# new.net
KiCad netlist of a schematic drawn in EAGLE
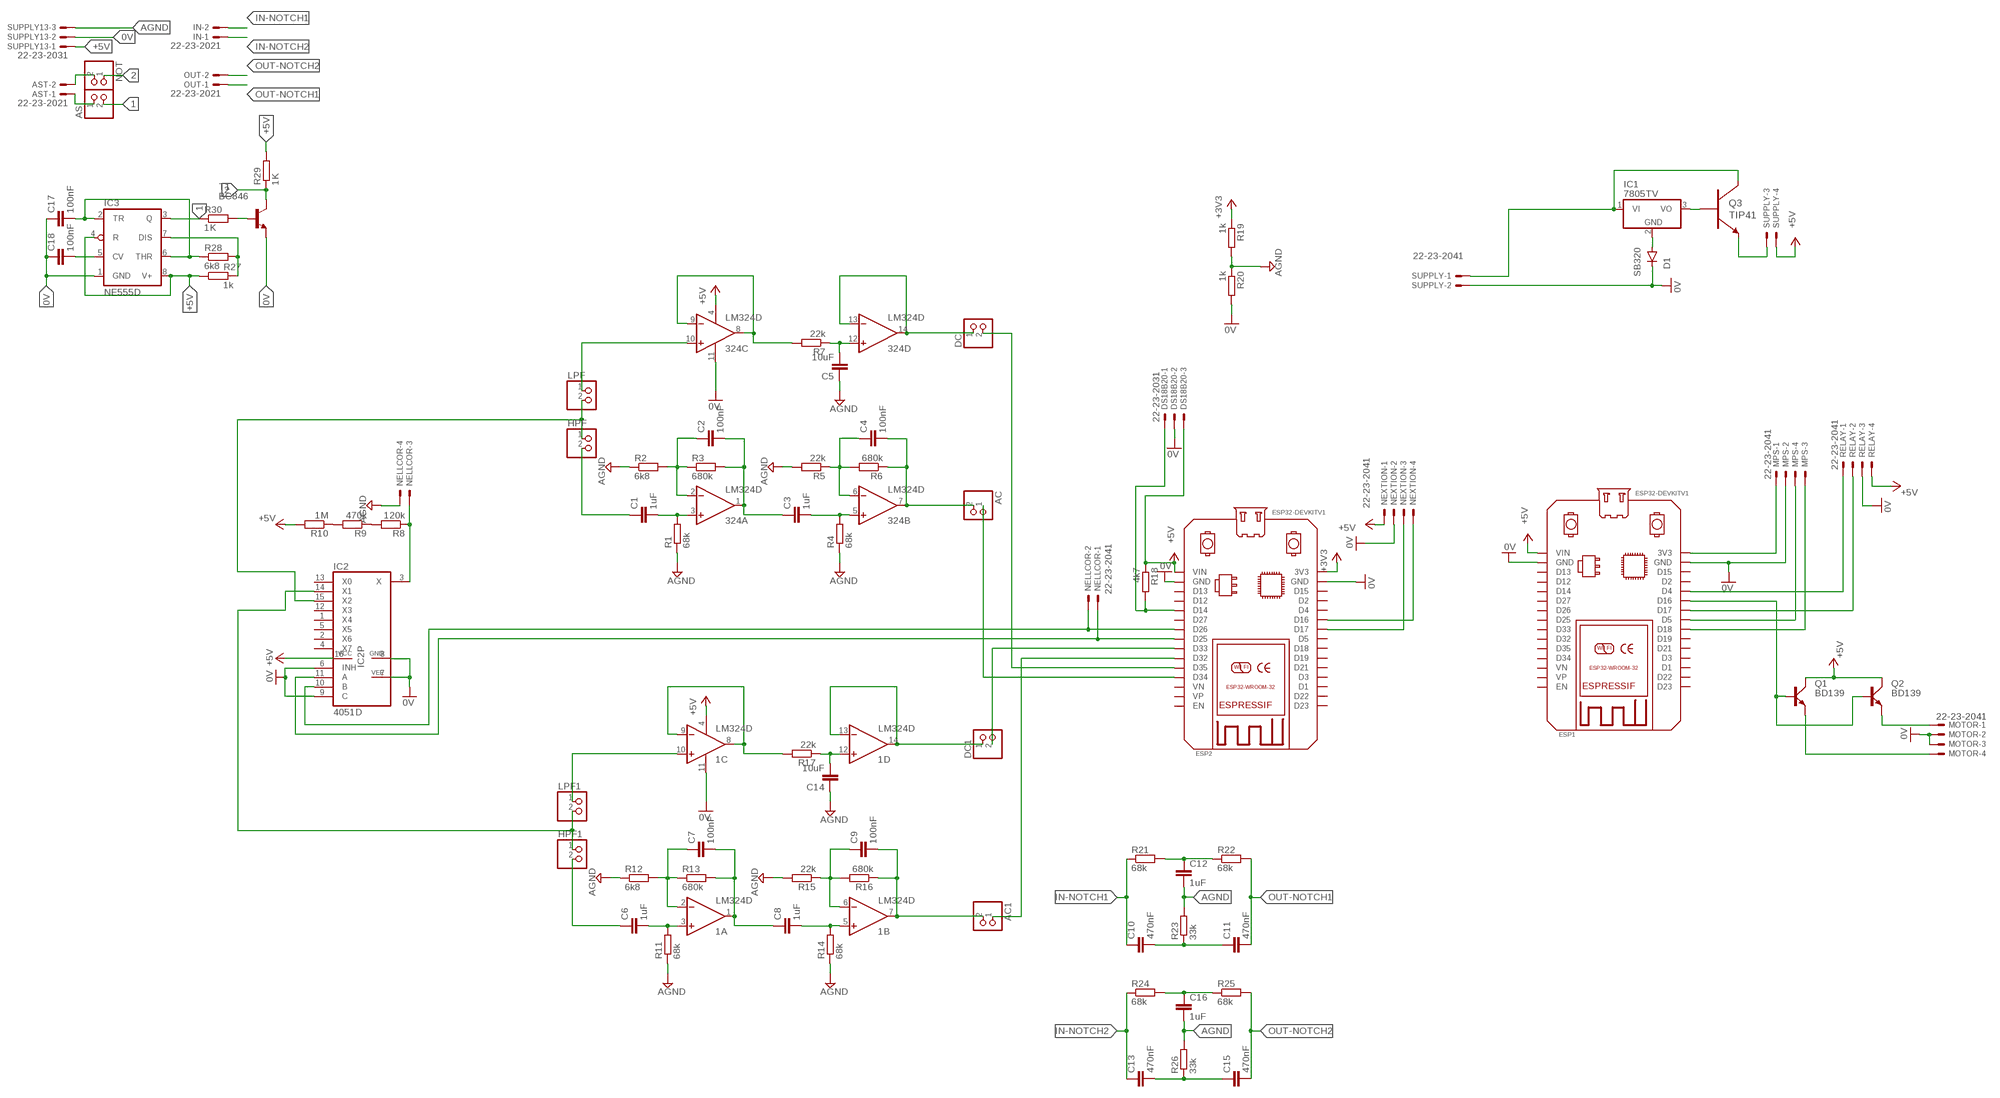
[diagram p0: schematic, sheet 1]

(export (version "E")
  (design (tool "Eeschema 10.0.6"))
  (components
    (comp (ref "1")
      (value "LM324D")
      (footprint "eagle-import:SO14")
      (libsource (lib "eagle-import") (part "LM324D"))
    )
    (comp (ref "324")
      (value "LM324D")
      (footprint "eagle-import:SO14")
      (libsource (lib "eagle-import") (part "LM324D"))
    )
    (comp (ref "AC")
      (value "PINHD-1X2")
      (footprint "eagle-import:1X02")
      (libsource (lib "eagle-import") (part "PINHD-1X2"))
    )
    (comp (ref "AC1")
      (value "PINHD-1X2")
      (footprint "eagle-import:1X02")
      (libsource (lib "eagle-import") (part "PINHD-1X2"))
    )
    (comp (ref "AS")
      (value "PINHD-1X2")
      (footprint "eagle-import:1X02")
      (libsource (lib "eagle-import") (part "PINHD-1X2"))
    )
    (comp (ref "AST")
      (value "22-23-2021")
      (footprint "eagle-import:22-23-2021")
      (fields (field (name "MF") "MOLEX"))
      (libsource (lib "eagle-import") (part "22-23-2021"))
    )
    (comp (ref "C1")
      (value "1uF")
      (footprint "eagle-import:C0603")
      (libsource (lib "eagle-import") (part "C-EUC0603"))
    )
    (comp (ref "C2")
      (value "100nF")
      (footprint "eagle-import:C0603")
      (libsource (lib "eagle-import") (part "C-EUC0603"))
    )
    (comp (ref "C3")
      (value "1uF")
      (footprint "eagle-import:C0603")
      (libsource (lib "eagle-import") (part "C-EUC0603"))
    )
    (comp (ref "C4")
      (value "100nF")
      (footprint "eagle-import:C0603")
      (libsource (lib "eagle-import") (part "C-EUC0603"))
    )
    (comp (ref "C5")
      (value "10uF")
      (footprint "eagle-import:C0603")
      (libsource (lib "eagle-import") (part "C-EUC0603"))
    )
    (comp (ref "C6")
      (value "1uF")
      (footprint "eagle-import:C0603")
      (libsource (lib "eagle-import") (part "C-EUC0603"))
    )
    (comp (ref "C7")
      (value "100nF")
      (footprint "eagle-import:C0603")
      (libsource (lib "eagle-import") (part "C-EUC0603"))
    )
    (comp (ref "C8")
      (value "1uF")
      (footprint "eagle-import:C0603")
      (libsource (lib "eagle-import") (part "C-EUC0603"))
    )
    (comp (ref "C9")
      (value "100nF")
      (footprint "eagle-import:C0603")
      (libsource (lib "eagle-import") (part "C-EUC0603"))
    )
    (comp (ref "C10")
      (value "470nF")
      (footprint "eagle-import:C0603")
      (libsource (lib "eagle-import") (part "C-EUC0603"))
    )
    (comp (ref "C11")
      (value "470nF")
      (footprint "eagle-import:C0603")
      (libsource (lib "eagle-import") (part "C-EUC0603"))
    )
    (comp (ref "C12")
      (value "1uF")
      (footprint "eagle-import:C0603")
      (libsource (lib "eagle-import") (part "C-EUC0603"))
    )
    (comp (ref "C13")
      (value "470nF")
      (footprint "eagle-import:C0603")
      (libsource (lib "eagle-import") (part "C-EUC0603"))
    )
    (comp (ref "C14")
      (value "10uF")
      (footprint "eagle-import:C0603")
      (libsource (lib "eagle-import") (part "C-EUC0603"))
    )
    (comp (ref "C15")
      (value "470nF")
      (footprint "eagle-import:C0603")
      (libsource (lib "eagle-import") (part "C-EUC0603"))
    )
    (comp (ref "C16")
      (value "1uF")
      (footprint "eagle-import:C0603")
      (libsource (lib "eagle-import") (part "C-EUC0603"))
    )
    (comp (ref "C17")
      (value "100nF")
      (footprint "eagle-import:C0603")
      (libsource (lib "eagle-import") (part "C-EUC0603"))
    )
    (comp (ref "C18")
      (value "100nF")
      (footprint "eagle-import:C0603")
      (libsource (lib "eagle-import") (part "C-EUC0603"))
    )
    (comp (ref "D1")
      (value "SB320")
      (footprint "eagle-import:DO201-15")
      (libsource (lib "eagle-import") (part "SB320"))
    )
    (comp (ref "DC")
      (value "PINHD-1X2")
      (footprint "eagle-import:1X02")
      (libsource (lib "eagle-import") (part "PINHD-1X2"))
    )
    (comp (ref "DC1")
      (value "PINHD-1X2")
      (footprint "eagle-import:1X02")
      (libsource (lib "eagle-import") (part "PINHD-1X2"))
    )
    (comp (ref "DS18B20")
      (value "22-23-2031")
      (footprint "eagle-import:22-23-2031")
      (fields (field (name "MF") "MOLEX"))
      (libsource (lib "eagle-import") (part "22-23-2031"))
    )
    (comp (ref "ESP1")
      (value "ESP32DEVKITV1")
      (footprint "eagle-import:ESP32-DEVKITV1")
      (libsource (lib "eagle-import") (part "ESP32DEVKITV1"))
    )
    (comp (ref "ESP2")
      (value "ESP32DEVKITV1")
      (footprint "eagle-import:ESP32-DEVKITV1")
      (libsource (lib "eagle-import") (part "ESP32DEVKITV1"))
    )
    (comp (ref "HPF")
      (value "PINHD-1X2")
      (footprint "eagle-import:1X02")
      (libsource (lib "eagle-import") (part "PINHD-1X2"))
    )
    (comp (ref "HPF1")
      (value "PINHD-1X2")
      (footprint "eagle-import:1X02")
      (libsource (lib "eagle-import") (part "PINHD-1X2"))
    )
    (comp (ref "IC1")
      (value "7805TV")
      (footprint "eagle-import:TO220V")
      (libsource (lib "eagle-import") (part "78TV05"))
    )
    (comp (ref "IC2")
      (value "4051D")
      (footprint "eagle-import:SO16")
      (libsource (lib "eagle-import") (part "4051D"))
    )
    (comp (ref "IC3")
      (value "NE555D")
      (footprint "eagle-import:SO08")
      (libsource (lib "eagle-import") (part "555DNE"))
    )
    (comp (ref "IN")
      (value "22-23-2021")
      (footprint "eagle-import:22-23-2021")
      (fields (field (name "MF") "MOLEX"))
      (libsource (lib "eagle-import") (part "22-23-2021"))
    )
    (comp (ref "LPF")
      (value "PINHD-1X2")
      (footprint "eagle-import:1X02")
      (libsource (lib "eagle-import") (part "PINHD-1X2"))
    )
    (comp (ref "LPF1")
      (value "PINHD-1X2")
      (footprint "eagle-import:1X02")
      (libsource (lib "eagle-import") (part "PINHD-1X2"))
    )
    (comp (ref "MOTOR")
      (value "22-23-2041")
      (footprint "eagle-import:22-23-2041")
      (fields (field (name "MF") "MOLEX"))
      (libsource (lib "eagle-import") (part "22-23-2041"))
    )
    (comp (ref "MPS")
      (value "22-23-2041")
      (footprint "eagle-import:22-23-2041")
      (fields (field (name "MF") "MOLEX"))
      (libsource (lib "eagle-import") (part "22-23-2041"))
    )
    (comp (ref "NELLCOR")
      (value "22-23-2041")
      (footprint "eagle-import:22-23-2041")
      (fields (field (name "MF") "MOLEX"))
      (libsource (lib "eagle-import") (part "22-23-2041"))
    )
    (comp (ref "NEXTION")
      (value "22-23-2041")
      (footprint "eagle-import:22-23-2041")
      (fields (field (name "MF") "MOLEX"))
      (libsource (lib "eagle-import") (part "22-23-2041"))
    )
    (comp (ref "NOT")
      (value "PINHD-1X2")
      (footprint "eagle-import:1X02")
      (libsource (lib "eagle-import") (part "PINHD-1X2"))
    )
    (comp (ref "OUT")
      (value "22-23-2021")
      (footprint "eagle-import:22-23-2021")
      (fields (field (name "MF") "MOLEX"))
      (libsource (lib "eagle-import") (part "22-23-2021"))
    )
    (comp (ref "Q1")
      (value "BD139")
      (footprint "eagle-import:TO126AV")
      (libsource (lib "eagle-import") (part "BD139"))
    )
    (comp (ref "Q2")
      (value "BD139")
      (footprint "eagle-import:TO126AV")
      (libsource (lib "eagle-import") (part "BD139"))
    )
    (comp (ref "Q3")
      (value "TIP41")
      (footprint "eagle-import:TO-220AB")
      (fields (field (name "MF") "ON Semiconductor"))
      (libsource (lib "eagle-import") (part "TIP41"))
    )
    (comp (ref "R1")
      (value "68k")
      (footprint "eagle-import:R0603")
      (libsource (lib "eagle-import") (part "R-EU_R0603"))
    )
    (comp (ref "R2")
      (value "6k8")
      (footprint "eagle-import:R0603")
      (libsource (lib "eagle-import") (part "R-EU_R0603"))
    )
    (comp (ref "R3")
      (value "680k")
      (footprint "eagle-import:R0603")
      (libsource (lib "eagle-import") (part "R-EU_R0603"))
    )
    (comp (ref "R4")
      (value "68k")
      (footprint "eagle-import:R0603")
      (libsource (lib "eagle-import") (part "R-EU_R0603"))
    )
    (comp (ref "R5")
      (value "22k")
      (footprint "eagle-import:R0603")
      (libsource (lib "eagle-import") (part "R-EU_R0603"))
    )
    (comp (ref "R6")
      (value "680k")
      (footprint "eagle-import:R0603")
      (libsource (lib "eagle-import") (part "R-EU_R0603"))
    )
    (comp (ref "R7")
      (value "22k")
      (footprint "eagle-import:R0603")
      (libsource (lib "eagle-import") (part "R-EU_R0603"))
    )
    (comp (ref "R8")
      (value "120k")
      (footprint "eagle-import:R0603")
      (libsource (lib "eagle-import") (part "R-EU_R0603"))
    )
    (comp (ref "R9")
      (value "470k")
      (footprint "eagle-import:R0603")
      (libsource (lib "eagle-import") (part "R-EU_R0603"))
    )
    (comp (ref "R10")
      (value "1M")
      (footprint "eagle-import:R0603")
      (libsource (lib "eagle-import") (part "R-EU_R0603"))
    )
    (comp (ref "R11")
      (value "68k")
      (footprint "eagle-import:R0603")
      (libsource (lib "eagle-import") (part "R-EU_R0603"))
    )
    (comp (ref "R12")
      (value "6k8")
      (footprint "eagle-import:R0603")
      (libsource (lib "eagle-import") (part "R-EU_R0603"))
    )
    (comp (ref "R13")
      (value "680k")
      (footprint "eagle-import:R0603")
      (libsource (lib "eagle-import") (part "R-EU_R0603"))
    )
    (comp (ref "R14")
      (value "68k")
      (footprint "eagle-import:R0603")
      (libsource (lib "eagle-import") (part "R-EU_R0603"))
    )
    (comp (ref "R15")
      (value "22k")
      (footprint "eagle-import:R0603")
      (libsource (lib "eagle-import") (part "R-EU_R0603"))
    )
    (comp (ref "R16")
      (value "680k")
      (footprint "eagle-import:R0603")
      (libsource (lib "eagle-import") (part "R-EU_R0603"))
    )
    (comp (ref "R17")
      (value "22k")
      (footprint "eagle-import:R0603")
      (libsource (lib "eagle-import") (part "R-EU_R0603"))
    )
    (comp (ref "R18")
      (value "4k7")
      (footprint "eagle-import:R0603")
      (libsource (lib "eagle-import") (part "R-EU_R0603"))
    )
    (comp (ref "R19")
      (value "1k")
      (footprint "eagle-import:R0603")
      (libsource (lib "eagle-import") (part "R-EU_R0603"))
    )
    (comp (ref "R20")
      (value "1k")
      (footprint "eagle-import:R0603")
      (libsource (lib "eagle-import") (part "R-EU_R0603"))
    )
    (comp (ref "R21")
      (value "68k")
      (footprint "eagle-import:R0603")
      (libsource (lib "eagle-import") (part "R-EU_R0603"))
    )
    (comp (ref "R22")
      (value "68k")
      (footprint "eagle-import:R0603")
      (libsource (lib "eagle-import") (part "R-EU_R0603"))
    )
    (comp (ref "R23")
      (value "33k")
      (footprint "eagle-import:R0603")
      (libsource (lib "eagle-import") (part "R-EU_R0603"))
    )
    (comp (ref "R24")
      (value "68k")
      (footprint "eagle-import:R0603")
      (libsource (lib "eagle-import") (part "R-EU_R0603"))
    )
    (comp (ref "R25")
      (value "68k")
      (footprint "eagle-import:R0603")
      (libsource (lib "eagle-import") (part "R-EU_R0603"))
    )
    (comp (ref "R26")
      (value "33k")
      (footprint "eagle-import:R0603")
      (libsource (lib "eagle-import") (part "R-EU_R0603"))
    )
    (comp (ref "R27")
      (value "1k")
      (footprint "eagle-import:R0603")
      (libsource (lib "eagle-import") (part "R-EU_R0603"))
    )
    (comp (ref "R28")
      (value "6k8")
      (footprint "eagle-import:R0603")
      (libsource (lib "eagle-import") (part "R-EU_R0603"))
    )
    (comp (ref "R29")
      (value "1K")
      (footprint "eagle-import:R0603")
      (libsource (lib "eagle-import") (part "R-EU_R0603"))
    )
    (comp (ref "R30")
      (value "1K")
      (footprint "eagle-import:R0603")
      (libsource (lib "eagle-import") (part "R-EU_R0603"))
    )
    (comp (ref "RELAY")
      (value "22-23-2041")
      (footprint "eagle-import:22-23-2041")
      (fields (field (name "MF") "MOLEX"))
      (libsource (lib "eagle-import") (part "22-23-2041"))
    )
    (comp (ref "SUPPLY")
      (value "22-23-2041")
      (footprint "eagle-import:22-23-2041")
      (fields (field (name "MF") "MOLEX"))
      (libsource (lib "eagle-import") (part "22-23-2041"))
    )
    (comp (ref "SUPPLY13")
      (value "22-23-2031")
      (footprint "eagle-import:22-23-2031")
      (fields (field (name "MF") "MOLEX"))
      (libsource (lib "eagle-import") (part "22-23-2031"))
    )
    (comp (ref "T1")
      (value "BC846")
      (footprint "eagle-import:SOT23")
      (libsource (lib "eagle-import") (part "BC846"))
    )
  )
  (nets
    (net (code "1") (name "+3V3") (class "Default")
      (node (ref "ESP2") (pin "3V3") (pinfunction "3V3_3V3") (pintype "bidirectional"))
      (node (ref "R19") (pin "1") (pinfunction "1_1") (pintype "passive"))
    )
    (net (code "2") (name "+5V") (class "Default")
      (node (ref "1") (pin "4") (pinfunction "V+_4") (pintype "power_in"))
      (node (ref "324") (pin "4") (pinfunction "V+_4") (pintype "power_in"))
      (node (ref "DS18B20") (pin "3") (pinfunction "S_3") (pintype "passive"))
      (node (ref "ESP1") (pin "VIN") (pinfunction "VIN_VIN") (pintype "bidirectional"))
      (node (ref "ESP2") (pin "VIN") (pinfunction "VIN_VIN") (pintype "bidirectional"))
      (node (ref "IC2") (pin "16") (pinfunction "VCC_16") (pintype "power_in"))
      (node (ref "IC3") (pin "4") (pinfunction "R_4") (pintype "input"))
      (node (ref "IC3") (pin "8") (pinfunction "V+_8") (pintype "power_in"))
      (node (ref "NEXTION") (pin "1") (pinfunction "S_1") (pintype "passive"))
      (node (ref "Q1") (pin "C") (pinfunction "C_C") (pintype "passive"))
      (node (ref "Q2") (pin "C") (pinfunction "C_C") (pintype "passive"))
      (node (ref "R10") (pin "2") (pinfunction "2_2") (pintype "passive"))
      (node (ref "R18") (pin "1") (pinfunction "1_1") (pintype "passive"))
      (node (ref "R27") (pin "1") (pinfunction "1_1") (pintype "passive"))
      (node (ref "R29") (pin "2") (pinfunction "2_2") (pintype "passive"))
      (node (ref "RELAY") (pin "4") (pinfunction "S_4") (pintype "passive"))
      (node (ref "SUPPLY") (pin "4") (pinfunction "S_4") (pintype "passive"))
      (node (ref "SUPPLY13") (pin "1") (pinfunction "S_1") (pintype "passive"))
    )
    (net (code "3") (name "0V") (class "Default")
      (node (ref "1") (pin "11") (pinfunction "V-_11") (pintype "power_in"))
      (node (ref "324") (pin "11") (pinfunction "V-_11") (pintype "power_in"))
      (node (ref "C17") (pin "1") (pinfunction "1_1") (pintype "passive"))
      (node (ref "C18") (pin "1") (pinfunction "1_1") (pintype "passive"))
      (node (ref "D1") (pin "C") (pinfunction "C_C") (pintype "passive"))
      (node (ref "DS18B20") (pin "2") (pinfunction "S_2") (pintype "passive"))
      (node (ref "ESP1") (pin "GND") (pinfunction "GND_GND") (pintype "bidirectional"))
      (node (ref "ESP1") (pin "GND@1") (pinfunction "GND_GND@1") (pintype "bidirectional"))
      (node (ref "ESP2") (pin "GND") (pinfunction "GND_GND") (pintype "bidirectional"))
      (node (ref "ESP2") (pin "GND@1") (pinfunction "GND_GND@1") (pintype "bidirectional"))
      (node (ref "IC2") (pin "6") (pinfunction "INH_6") (pintype "input"))
      (node (ref "IC2") (pin "7") (pinfunction "VEE_7") (pintype "power_in"))
      (node (ref "IC2") (pin "8") (pinfunction "GND_8") (pintype "power_in"))
      (node (ref "IC2") (pin "9") (pinfunction "C_9") (pintype "input"))
      (node (ref "IC3") (pin "1") (pinfunction "GND_1") (pintype "power_in"))
      (node (ref "MOTOR") (pin "2") (pinfunction "S_2") (pintype "passive"))
      (node (ref "MOTOR") (pin "3") (pinfunction "S_3") (pintype "passive"))
      (node (ref "MPS") (pin "2") (pinfunction "S_2") (pintype "passive"))
      (node (ref "NEXTION") (pin "2") (pinfunction "S_2") (pintype "passive"))
      (node (ref "R20") (pin "2") (pinfunction "2_2") (pintype "passive"))
      (node (ref "RELAY") (pin "3") (pinfunction "S_3") (pintype "passive"))
      (node (ref "SUPPLY") (pin "2") (pinfunction "S_2") (pintype "passive"))
      (node (ref "SUPPLY13") (pin "2") (pinfunction "S_2") (pintype "passive"))
      (node (ref "T1") (pin "2") (pinfunction "E_2") (pintype "passive"))
    )
    (net (code "4") (name "1") (class "Default")
      (node (ref "AS") (pin "2") (pinfunction "2_2") (pintype "passive"))
      (node (ref "IC3") (pin "3") (pinfunction "Q_3") (pintype "output"))
      (node (ref "R30") (pin "1") (pinfunction "1_1") (pintype "passive"))
    )
    (net (code "5") (name "2") (class "Default")
      (node (ref "NOT") (pin "1") (pinfunction "1_1") (pintype "passive"))
      (node (ref "R29") (pin "1") (pinfunction "1_1") (pintype "passive"))
      (node (ref "T1") (pin "3") (pinfunction "C_3") (pintype "passive"))
    )
    (net (code "6") (name "AGND") (class "Default")
      (node (ref "C12") (pin "2") (pinfunction "2_2") (pintype "passive"))
      (node (ref "C14") (pin "1") (pinfunction "1_1") (pintype "passive"))
      (node (ref "C16") (pin "2") (pinfunction "2_2") (pintype "passive"))
      (node (ref "C5") (pin "1") (pinfunction "1_1") (pintype "passive"))
      (node (ref "NELLCOR") (pin "4") (pinfunction "S_4") (pintype "passive"))
      (node (ref "R1") (pin "1") (pinfunction "1_1") (pintype "passive"))
      (node (ref "R11") (pin "1") (pinfunction "1_1") (pintype "passive"))
      (node (ref "R12") (pin "1") (pinfunction "1_1") (pintype "passive"))
      (node (ref "R14") (pin "1") (pinfunction "1_1") (pintype "passive"))
      (node (ref "R15") (pin "2") (pinfunction "2_2") (pintype "passive"))
      (node (ref "R19") (pin "2") (pinfunction "2_2") (pintype "passive"))
      (node (ref "R2") (pin "1") (pinfunction "1_1") (pintype "passive"))
      (node (ref "R20") (pin "1") (pinfunction "1_1") (pintype "passive"))
      (node (ref "R23") (pin "2") (pinfunction "2_2") (pintype "passive"))
      (node (ref "R26") (pin "2") (pinfunction "2_2") (pintype "passive"))
      (node (ref "R4") (pin "1") (pinfunction "1_1") (pintype "passive"))
      (node (ref "R5") (pin "2") (pinfunction "2_2") (pintype "passive"))
      (node (ref "SUPPLY13") (pin "3") (pinfunction "S_3") (pintype "passive"))
    )
    (net (code "7") (name "IN-NOTCH1") (class "Default")
      (node (ref "C10") (pin "1") (pinfunction "1_1") (pintype "passive"))
      (node (ref "IN") (pin "2") (pinfunction "S_2") (pintype "passive"))
      (node (ref "R21") (pin "1") (pinfunction "1_1") (pintype "passive"))
    )
    (net (code "8") (name "IN-NOTCH2") (class "Default")
      (node (ref "C13") (pin "1") (pinfunction "1_1") (pintype "passive"))
      (node (ref "IN") (pin "1") (pinfunction "S_1") (pintype "passive"))
      (node (ref "R24") (pin "1") (pinfunction "1_1") (pintype "passive"))
    )
    (net (code "9") (name "Net-(1A-+IN)") (class "Default")
      (node (ref "1") (pin "3") (pinfunction "+IN_3") (pintype "input"))
      (node (ref "C6") (pin "2") (pinfunction "2_2") (pintype "passive"))
      (node (ref "R11") (pin "2") (pinfunction "2_2") (pintype "passive"))
    )
    (net (code "10") (name "Net-(1A--IN)") (class "Default")
      (node (ref "1") (pin "2") (pinfunction "-IN_2") (pintype "input"))
      (node (ref "C7") (pin "1") (pinfunction "1_1") (pintype "passive"))
      (node (ref "R12") (pin "2") (pinfunction "2_2") (pintype "passive"))
      (node (ref "R13") (pin "1") (pinfunction "1_1") (pintype "passive"))
    )
    (net (code "11") (name "Net-(1A-OUT)") (class "Default")
      (node (ref "1") (pin "1") (pinfunction "OUT_1") (pintype "output"))
      (node (ref "C7") (pin "2") (pinfunction "2_2") (pintype "passive"))
      (node (ref "C8") (pin "1") (pinfunction "1_1") (pintype "passive"))
      (node (ref "R13") (pin "2") (pinfunction "2_2") (pintype "passive"))
    )
    (net (code "12") (name "Net-(1B-+IN)") (class "Default")
      (node (ref "1") (pin "5") (pinfunction "+IN_5") (pintype "input"))
      (node (ref "C8") (pin "2") (pinfunction "2_2") (pintype "passive"))
      (node (ref "R14") (pin "2") (pinfunction "2_2") (pintype "passive"))
    )
    (net (code "13") (name "Net-(1B--IN)") (class "Default")
      (node (ref "1") (pin "6") (pinfunction "-IN_6") (pintype "input"))
      (node (ref "C9") (pin "1") (pinfunction "1_1") (pintype "passive"))
      (node (ref "R15") (pin "1") (pinfunction "1_1") (pintype "passive"))
      (node (ref "R16") (pin "2") (pinfunction "2_2") (pintype "passive"))
    )
    (net (code "14") (name "Net-(1B-OUT)") (class "Default")
      (node (ref "1") (pin "7") (pinfunction "OUT_7") (pintype "output"))
      (node (ref "AC1") (pin "2") (pinfunction "2_2") (pintype "passive"))
      (node (ref "C9") (pin "2") (pinfunction "2_2") (pintype "passive"))
      (node (ref "R16") (pin "1") (pinfunction "1_1") (pintype "passive"))
    )
    (net (code "15") (name "Net-(1C-+IN)") (class "Default")
      (node (ref "1") (pin "10") (pinfunction "+IN_10") (pintype "input"))
      (node (ref "LPF1") (pin "1") (pinfunction "1_1") (pintype "passive"))
    )
    (net (code "16") (name "Net-(1C--IN)") (class "Default")
      (node (ref "1") (pin "8") (pinfunction "OUT_8") (pintype "output"))
      (node (ref "1") (pin "9") (pinfunction "-IN_9") (pintype "input"))
      (node (ref "R17") (pin "2") (pinfunction "2_2") (pintype "passive"))
    )
    (net (code "17") (name "Net-(1D-+IN)") (class "Default")
      (node (ref "1") (pin "12") (pinfunction "+IN_12") (pintype "input"))
      (node (ref "C14") (pin "2") (pinfunction "2_2") (pintype "passive"))
      (node (ref "R17") (pin "1") (pinfunction "1_1") (pintype "passive"))
    )
    (net (code "18") (name "Net-(1D--IN)") (class "Default")
      (node (ref "1") (pin "13") (pinfunction "-IN_13") (pintype "input"))
      (node (ref "1") (pin "14") (pinfunction "OUT_14") (pintype "output"))
      (node (ref "DC1") (pin "1") (pinfunction "1_1") (pintype "passive"))
    )
    (net (code "19") (name "Net-(324A-+IN)") (class "Default")
      (node (ref "324") (pin "3") (pinfunction "+IN_3") (pintype "input"))
      (node (ref "C1") (pin "2") (pinfunction "2_2") (pintype "passive"))
      (node (ref "R1") (pin "2") (pinfunction "2_2") (pintype "passive"))
    )
    (net (code "20") (name "Net-(324A--IN)") (class "Default")
      (node (ref "324") (pin "2") (pinfunction "-IN_2") (pintype "input"))
      (node (ref "C2") (pin "1") (pinfunction "1_1") (pintype "passive"))
      (node (ref "R2") (pin "2") (pinfunction "2_2") (pintype "passive"))
      (node (ref "R3") (pin "1") (pinfunction "1_1") (pintype "passive"))
    )
    (net (code "21") (name "Net-(324A-OUT)") (class "Default")
      (node (ref "324") (pin "1") (pinfunction "OUT_1") (pintype "output"))
      (node (ref "C2") (pin "2") (pinfunction "2_2") (pintype "passive"))
      (node (ref "C3") (pin "1") (pinfunction "1_1") (pintype "passive"))
      (node (ref "R3") (pin "2") (pinfunction "2_2") (pintype "passive"))
    )
    (net (code "22") (name "Net-(324B-+IN)") (class "Default")
      (node (ref "324") (pin "5") (pinfunction "+IN_5") (pintype "input"))
      (node (ref "C3") (pin "2") (pinfunction "2_2") (pintype "passive"))
      (node (ref "R4") (pin "2") (pinfunction "2_2") (pintype "passive"))
    )
    (net (code "23") (name "Net-(324B--IN)") (class "Default")
      (node (ref "324") (pin "6") (pinfunction "-IN_6") (pintype "input"))
      (node (ref "C4") (pin "1") (pinfunction "1_1") (pintype "passive"))
      (node (ref "R5") (pin "1") (pinfunction "1_1") (pintype "passive"))
      (node (ref "R6") (pin "2") (pinfunction "2_2") (pintype "passive"))
    )
    (net (code "24") (name "Net-(324B-OUT)") (class "Default")
      (node (ref "324") (pin "7") (pinfunction "OUT_7") (pintype "output"))
      (node (ref "AC") (pin "2") (pinfunction "2_2") (pintype "passive"))
      (node (ref "C4") (pin "2") (pinfunction "2_2") (pintype "passive"))
      (node (ref "R6") (pin "1") (pinfunction "1_1") (pintype "passive"))
    )
    (net (code "25") (name "Net-(324C-+IN)") (class "Default")
      (node (ref "324") (pin "10") (pinfunction "+IN_10") (pintype "input"))
      (node (ref "LPF") (pin "1") (pinfunction "1_1") (pintype "passive"))
    )
    (net (code "26") (name "Net-(324C--IN)") (class "Default")
      (node (ref "324") (pin "8") (pinfunction "OUT_8") (pintype "output"))
      (node (ref "324") (pin "9") (pinfunction "-IN_9") (pintype "input"))
      (node (ref "R7") (pin "2") (pinfunction "2_2") (pintype "passive"))
    )
    (net (code "27") (name "Net-(324D-+IN)") (class "Default")
      (node (ref "324") (pin "12") (pinfunction "+IN_12") (pintype "input"))
      (node (ref "C5") (pin "2") (pinfunction "2_2") (pintype "passive"))
      (node (ref "R7") (pin "1") (pinfunction "1_1") (pintype "passive"))
    )
    (net (code "28") (name "Net-(324D--IN)") (class "Default")
      (node (ref "324") (pin "13") (pinfunction "-IN_13") (pintype "input"))
      (node (ref "324") (pin "14") (pinfunction "OUT_14") (pintype "output"))
      (node (ref "DC") (pin "1") (pinfunction "1_1") (pintype "passive"))
    )
    (net (code "29") (name "Net-(AC-Pad1)") (class "Default")
      (node (ref "AC") (pin "1") (pinfunction "1_1") (pintype "passive"))
      (node (ref "ESP2") (pin "D34") (pinfunction "D34_D34") (pintype "bidirectional"))
    )
    (net (code "30") (name "Net-(AC1-Pad1)") (class "Default")
      (node (ref "AC1") (pin "1") (pinfunction "1_1") (pintype "passive"))
      (node (ref "ESP2") (pin "D32") (pinfunction "D32_D32") (pintype "bidirectional"))
    )
    (net (code "31") (name "Net-(ASTA-S)") (class "Default")
      (node (ref "AS") (pin "1") (pinfunction "1_1") (pintype "passive"))
      (node (ref "AST") (pin "1") (pinfunction "S_1") (pintype "passive"))
    )
    (net (code "32") (name "Net-(ASTB-S)") (class "Default")
      (node (ref "AST") (pin "2") (pinfunction "S_2") (pintype "passive"))
      (node (ref "NOT") (pin "2") (pinfunction "2_2") (pintype "passive"))
    )
    (net (code "33") (name "Net-(C1-Pad1)") (class "Default")
      (node (ref "C1") (pin "1") (pinfunction "1_1") (pintype "passive"))
      (node (ref "HPF") (pin "2") (pinfunction "2_2") (pintype "passive"))
    )
    (net (code "34") (name "Net-(C6-Pad1)") (class "Default")
      (node (ref "C6") (pin "1") (pinfunction "1_1") (pintype "passive"))
      (node (ref "HPF1") (pin "2") (pinfunction "2_2") (pintype "passive"))
    )
    (net (code "35") (name "Net-(C10-Pad2)") (class "Default")
      (node (ref "C10") (pin "2") (pinfunction "2_2") (pintype "passive"))
      (node (ref "C11") (pin "1") (pinfunction "1_1") (pintype "passive"))
      (node (ref "R23") (pin "1") (pinfunction "1_1") (pintype "passive"))
    )
    (net (code "36") (name "Net-(C12-Pad1)") (class "Default")
      (node (ref "C12") (pin "1") (pinfunction "1_1") (pintype "passive"))
      (node (ref "R21") (pin "2") (pinfunction "2_2") (pintype "passive"))
      (node (ref "R22") (pin "1") (pinfunction "1_1") (pintype "passive"))
    )
    (net (code "37") (name "Net-(C13-Pad2)") (class "Default")
      (node (ref "C13") (pin "2") (pinfunction "2_2") (pintype "passive"))
      (node (ref "C15") (pin "1") (pinfunction "1_1") (pintype "passive"))
      (node (ref "R26") (pin "1") (pinfunction "1_1") (pintype "passive"))
    )
    (net (code "38") (name "Net-(C16-Pad1)") (class "Default")
      (node (ref "C16") (pin "1") (pinfunction "1_1") (pintype "passive"))
      (node (ref "R24") (pin "2") (pinfunction "2_2") (pintype "passive"))
      (node (ref "R25") (pin "1") (pinfunction "1_1") (pintype "passive"))
    )
    (net (code "39") (name "Net-(DC-Pad2)") (class "Default")
      (node (ref "DC") (pin "2") (pinfunction "2_2") (pintype "passive"))
      (node (ref "ESP2") (pin "D35") (pinfunction "D35_D35") (pintype "bidirectional"))
    )
    (net (code "40") (name "Net-(DC1-Pad2)") (class "Default")
      (node (ref "DC1") (pin "2") (pinfunction "2_2") (pintype "passive"))
      (node (ref "ESP2") (pin "D33") (pinfunction "D33_D33") (pintype "bidirectional"))
    )
    (net (code "41") (name "Net-(DS18B20A-S)") (class "Default")
      (node (ref "DS18B20") (pin "1") (pinfunction "S_1") (pintype "passive"))
      (node (ref "ESP2") (pin "D14") (pinfunction "D14_D14") (pintype "bidirectional"))
      (node (ref "R18") (pin "2") (pinfunction "2_2") (pintype "passive"))
    )
    (net (code "42") (name "Net-(ESP1-PadD16)") (class "Default")
      (node (ref "ESP1") (pin "D16") (pinfunction "D16_D16") (pintype "bidirectional"))
      (node (ref "Q1") (pin "B") (pinfunction "B_B") (pintype "passive"))
      (node (ref "Q2") (pin "B") (pinfunction "B_B") (pintype "passive"))
    )
    (net (code "43") (name "Net-(IC1-GND)") (class "Default")
      (node (ref "D1") (pin "A") (pinfunction "A_A") (pintype "passive"))
      (node (ref "IC1") (pin "2") (pinfunction "GND_2") (pintype "passive"))
    )
    (net (code "44") (name "Net-(IC1-VI)") (class "Default")
      (node (ref "IC1") (pin "1") (pinfunction "VI_1") (pintype "input"))
      (node (ref "Q3") (pin "2") (pinfunction "C_2") (pintype "passive"))
      (node (ref "SUPPLY") (pin "1") (pinfunction "S_1") (pintype "passive"))
    )
    (net (code "45") (name "Net-(IC1-VO)") (class "Default")
      (node (ref "IC1") (pin "3") (pinfunction "VO_3") (pintype "passive"))
      (node (ref "Q3") (pin "1") (pinfunction "B_1") (pintype "passive"))
    )
    (net (code "46") (name "Net-(IC2A-A)") (class "Default")
      (node (ref "ESP2") (pin "D25") (pinfunction "D25_D25") (pintype "bidirectional"))
      (node (ref "IC2") (pin "11") (pinfunction "A_11") (pintype "input"))
      (node (ref "NELLCOR") (pin "1") (pinfunction "S_1") (pintype "passive"))
    )
    (net (code "47") (name "Net-(IC2A-B)") (class "Default")
      (node (ref "ESP2") (pin "D26") (pinfunction "D26_D26") (pintype "bidirectional"))
      (node (ref "IC2") (pin "10") (pinfunction "B_10") (pintype "input"))
      (node (ref "NELLCOR") (pin "2") (pinfunction "S_2") (pintype "passive"))
    )
    (net (code "48") (name "Net-(IC2A-X)") (class "Default")
      (node (ref "IC2") (pin "3") (pinfunction "X_3") (pintype "bidirectional"))
      (node (ref "NELLCOR") (pin "3") (pinfunction "S_3") (pintype "passive"))
      (node (ref "R8") (pin "1") (pinfunction "1_1") (pintype "passive"))
    )
    (net (code "49") (name "Net-(IC2A-X1)") (class "Default")
      (node (ref "HPF1") (pin "1") (pinfunction "1_1") (pintype "passive"))
      (node (ref "IC2") (pin "14") (pinfunction "X1_14") (pintype "bidirectional"))
      (node (ref "LPF1") (pin "2") (pinfunction "2_2") (pintype "passive"))
    )
    (net (code "50") (name "Net-(IC2A-X2)") (class "Default")
      (node (ref "HPF") (pin "1") (pinfunction "1_1") (pintype "passive"))
      (node (ref "IC2") (pin "15") (pinfunction "X2_15") (pintype "bidirectional"))
      (node (ref "LPF") (pin "2") (pinfunction "2_2") (pintype "passive"))
    )
    (net (code "51") (name "Net-(IC3-CV)") (class "Default")
      (node (ref "C18") (pin "2") (pinfunction "2_2") (pintype "passive"))
      (node (ref "IC3") (pin "5") (pinfunction "CV_5") (pintype "input"))
    )
    (net (code "52") (name "Net-(IC3-DIS)") (class "Default")
      (node (ref "IC3") (pin "7") (pinfunction "DIS_7") (pintype "input"))
      (node (ref "R27") (pin "2") (pinfunction "2_2") (pintype "passive"))
      (node (ref "R28") (pin "2") (pinfunction "2_2") (pintype "passive"))
    )
    (net (code "53") (name "Net-(IC3-THR)") (class "Default")
      (node (ref "C17") (pin "2") (pinfunction "2_2") (pintype "passive"))
      (node (ref "IC3") (pin "2") (pinfunction "TR_2") (pintype "input"))
      (node (ref "IC3") (pin "6") (pinfunction "THR_6") (pintype "input"))
      (node (ref "R28") (pin "1") (pinfunction "1_1") (pintype "passive"))
    )
    (net (code "54") (name "Net-(MOTORA-S)") (class "Default")
      (node (ref "MOTOR") (pin "1") (pinfunction "S_1") (pintype "passive"))
      (node (ref "Q2") (pin "E") (pinfunction "E_E") (pintype "passive"))
    )
    (net (code "55") (name "Net-(MOTORD-S)") (class "Default")
      (node (ref "MOTOR") (pin "4") (pinfunction "S_4") (pintype "passive"))
      (node (ref "Q1") (pin "E") (pinfunction "E_E") (pintype "passive"))
    )
    (net (code "56") (name "Net-(MPSA-S)") (class "Default")
      (node (ref "ESP1") (pin "3V3") (pinfunction "3V3_3V3") (pintype "bidirectional"))
      (node (ref "MPS") (pin "1") (pinfunction "S_1") (pintype "passive"))
    )
    (net (code "57") (name "Net-(MPSC-S)") (class "Default")
      (node (ref "ESP1") (pin "D18") (pinfunction "D18_D18") (pintype "bidirectional"))
      (node (ref "MPS") (pin "3") (pinfunction "S_3") (pintype "passive"))
    )
    (net (code "58") (name "Net-(MPSD-S)") (class "Default")
      (node (ref "ESP1") (pin "D5") (pinfunction "D5_D5") (pintype "bidirectional"))
      (node (ref "MPS") (pin "4") (pinfunction "S_4") (pintype "passive"))
    )
    (net (code "59") (name "Net-(NEXTIONC-S)") (class "Default")
      (node (ref "ESP2") (pin "D17") (pinfunction "D17_D17") (pintype "bidirectional"))
      (node (ref "NEXTION") (pin "3") (pinfunction "S_3") (pintype "passive"))
    )
    (net (code "60") (name "Net-(NEXTIOND-S)") (class "Default")
      (node (ref "ESP2") (pin "D16") (pinfunction "D16_D16") (pintype "bidirectional"))
      (node (ref "NEXTION") (pin "4") (pinfunction "S_4") (pintype "passive"))
    )
    (net (code "61") (name "Net-(Q3-E)") (class "Default")
      (node (ref "Q3") (pin "3") (pinfunction "E_3") (pintype "passive"))
      (node (ref "SUPPLY") (pin "3") (pinfunction "S_3") (pintype "passive"))
    )
    (net (code "62") (name "Net-(R8-Pad2)") (class "Default")
      (node (ref "R8") (pin "2") (pinfunction "2_2") (pintype "passive"))
      (node (ref "R9") (pin "1") (pinfunction "1_1") (pintype "passive"))
    )
    (net (code "63") (name "Net-(R10-Pad1)") (class "Default")
      (node (ref "R10") (pin "1") (pinfunction "1_1") (pintype "passive"))
      (node (ref "R9") (pin "2") (pinfunction "2_2") (pintype "passive"))
    )
    (net (code "64") (name "Net-(RELAYA-S)") (class "Default")
      (node (ref "ESP1") (pin "D4") (pinfunction "D4_D4") (pintype "bidirectional"))
      (node (ref "RELAY") (pin "1") (pinfunction "S_1") (pintype "passive"))
    )
    (net (code "65") (name "Net-(RELAYB-S)") (class "Default")
      (node (ref "ESP1") (pin "D17") (pinfunction "D17_D17") (pintype "bidirectional"))
      (node (ref "RELAY") (pin "2") (pinfunction "S_2") (pintype "passive"))
    )
    (net (code "66") (name "Net-(T1-B)") (class "Default")
      (node (ref "R30") (pin "2") (pinfunction "2_2") (pintype "passive"))
      (node (ref "T1") (pin "1") (pinfunction "B_1") (pintype "passive"))
    )
    (net (code "67") (name "OUT-NOTCH1") (class "Default")
      (node (ref "C11") (pin "2") (pinfunction "2_2") (pintype "passive"))
      (node (ref "OUT") (pin "1") (pinfunction "S_1") (pintype "passive"))
      (node (ref "R22") (pin "2") (pinfunction "2_2") (pintype "passive"))
    )
    (net (code "68") (name "OUT-NOTCH2") (class "Default")
      (node (ref "C15") (pin "2") (pinfunction "2_2") (pintype "passive"))
      (node (ref "OUT") (pin "2") (pinfunction "S_2") (pintype "passive"))
      (node (ref "R25") (pin "2") (pinfunction "2_2") (pintype "passive"))
    )
    (net (code "69") (name "unconnected-(ESP1-PadD1)") (class "Default")
      (node (ref "ESP1") (pin "D1") (pinfunction "D1_D1") (pintype "bidirectional"))
    )
    (net (code "70") (name "unconnected-(ESP1-PadD2)") (class "Default")
      (node (ref "ESP1") (pin "D2") (pinfunction "D2_D2") (pintype "bidirectional"))
    )
    (net (code "71") (name "unconnected-(ESP1-PadD3)") (class "Default")
      (node (ref "ESP1") (pin "D3") (pinfunction "D3_D3") (pintype "bidirectional"))
    )
    (net (code "72") (name "unconnected-(ESP1-PadD12)") (class "Default")
      (node (ref "ESP1") (pin "D12") (pinfunction "D12_D12") (pintype "bidirectional"))
    )
    (net (code "73") (name "unconnected-(ESP1-PadD13)") (class "Default")
      (node (ref "ESP1") (pin "D13") (pinfunction "D13_D13") (pintype "bidirectional"))
    )
    (net (code "74") (name "unconnected-(ESP1-PadD14)") (class "Default")
      (node (ref "ESP1") (pin "D14") (pinfunction "D14_D14") (pintype "bidirectional"))
    )
    (net (code "75") (name "unconnected-(ESP1-PadD15)") (class "Default")
      (node (ref "ESP1") (pin "D15") (pinfunction "D15_D15") (pintype "bidirectional"))
    )
    (net (code "76") (name "unconnected-(ESP1-PadD19)") (class "Default")
      (node (ref "ESP1") (pin "D19") (pinfunction "D19_D19") (pintype "bidirectional"))
    )
    (net (code "77") (name "unconnected-(ESP1-PadD21)") (class "Default")
      (node (ref "ESP1") (pin "D21") (pinfunction "D21_D21") (pintype "bidirectional"))
    )
    (net (code "78") (name "unconnected-(ESP1-PadD22)") (class "Default")
      (node (ref "ESP1") (pin "D22") (pinfunction "D22_D22") (pintype "bidirectional"))
    )
    (net (code "79") (name "unconnected-(ESP1-PadD23)") (class "Default")
      (node (ref "ESP1") (pin "D23") (pinfunction "D23_D23") (pintype "bidirectional"))
    )
    (net (code "80") (name "unconnected-(ESP1-PadD25)") (class "Default")
      (node (ref "ESP1") (pin "D25") (pinfunction "D25_D25") (pintype "bidirectional"))
    )
    (net (code "81") (name "unconnected-(ESP1-PadD26)") (class "Default")
      (node (ref "ESP1") (pin "D26") (pinfunction "D26_D26") (pintype "bidirectional"))
    )
    (net (code "82") (name "unconnected-(ESP1-PadD27)") (class "Default")
      (node (ref "ESP1") (pin "D27") (pinfunction "D27_D27") (pintype "bidirectional"))
    )
    (net (code "83") (name "unconnected-(ESP1-PadD32)") (class "Default")
      (node (ref "ESP1") (pin "D32") (pinfunction "D32_D32") (pintype "bidirectional"))
    )
    (net (code "84") (name "unconnected-(ESP1-PadD33)") (class "Default")
      (node (ref "ESP1") (pin "D33") (pinfunction "D33_D33") (pintype "bidirectional"))
    )
    (net (code "85") (name "unconnected-(ESP1-PadD34)") (class "Default")
      (node (ref "ESP1") (pin "D34") (pinfunction "D34_D34") (pintype "bidirectional"))
    )
    (net (code "86") (name "unconnected-(ESP1-PadD35)") (class "Default")
      (node (ref "ESP1") (pin "D35") (pinfunction "D35_D35") (pintype "bidirectional"))
    )
    (net (code "87") (name "unconnected-(ESP1-PadEN)") (class "Default")
      (node (ref "ESP1") (pin "EN") (pinfunction "EN_EN") (pintype "bidirectional"))
    )
    (net (code "88") (name "unconnected-(ESP1-PadVN)") (class "Default")
      (node (ref "ESP1") (pin "VN") (pinfunction "VN_VN") (pintype "bidirectional"))
    )
    (net (code "89") (name "unconnected-(ESP1-PadVP)") (class "Default")
      (node (ref "ESP1") (pin "VP") (pinfunction "VP_VP") (pintype "bidirectional"))
    )
    (net (code "90") (name "unconnected-(ESP2-PadD1)") (class "Default")
      (node (ref "ESP2") (pin "D1") (pinfunction "D1_D1") (pintype "bidirectional"))
    )
    (net (code "91") (name "unconnected-(ESP2-PadD2)") (class "Default")
      (node (ref "ESP2") (pin "D2") (pinfunction "D2_D2") (pintype "bidirectional"))
    )
    (net (code "92") (name "unconnected-(ESP2-PadD3)") (class "Default")
      (node (ref "ESP2") (pin "D3") (pinfunction "D3_D3") (pintype "bidirectional"))
    )
    (net (code "93") (name "unconnected-(ESP2-PadD4)") (class "Default")
      (node (ref "ESP2") (pin "D4") (pinfunction "D4_D4") (pintype "bidirectional"))
    )
    (net (code "94") (name "unconnected-(ESP2-PadD5)") (class "Default")
      (node (ref "ESP2") (pin "D5") (pinfunction "D5_D5") (pintype "bidirectional"))
    )
    (net (code "95") (name "unconnected-(ESP2-PadD12)") (class "Default")
      (node (ref "ESP2") (pin "D12") (pinfunction "D12_D12") (pintype "bidirectional"))
    )
    (net (code "96") (name "unconnected-(ESP2-PadD13)") (class "Default")
      (node (ref "ESP2") (pin "D13") (pinfunction "D13_D13") (pintype "bidirectional"))
    )
    (net (code "97") (name "unconnected-(ESP2-PadD15)") (class "Default")
      (node (ref "ESP2") (pin "D15") (pinfunction "D15_D15") (pintype "bidirectional"))
    )
    (net (code "98") (name "unconnected-(ESP2-PadD18)") (class "Default")
      (node (ref "ESP2") (pin "D18") (pinfunction "D18_D18") (pintype "bidirectional"))
    )
    (net (code "99") (name "unconnected-(ESP2-PadD19)") (class "Default")
      (node (ref "ESP2") (pin "D19") (pinfunction "D19_D19") (pintype "bidirectional"))
    )
    (net (code "100") (name "unconnected-(ESP2-PadD21)") (class "Default")
      (node (ref "ESP2") (pin "D21") (pinfunction "D21_D21") (pintype "bidirectional"))
    )
    (net (code "101") (name "unconnected-(ESP2-PadD22)") (class "Default")
      (node (ref "ESP2") (pin "D22") (pinfunction "D22_D22") (pintype "bidirectional"))
    )
    (net (code "102") (name "unconnected-(ESP2-PadD23)") (class "Default")
      (node (ref "ESP2") (pin "D23") (pinfunction "D23_D23") (pintype "bidirectional"))
    )
    (net (code "103") (name "unconnected-(ESP2-PadD27)") (class "Default")
      (node (ref "ESP2") (pin "D27") (pinfunction "D27_D27") (pintype "bidirectional"))
    )
    (net (code "104") (name "unconnected-(ESP2-PadEN)") (class "Default")
      (node (ref "ESP2") (pin "EN") (pinfunction "EN_EN") (pintype "bidirectional"))
    )
    (net (code "105") (name "unconnected-(ESP2-PadVN)") (class "Default")
      (node (ref "ESP2") (pin "VN") (pinfunction "VN_VN") (pintype "bidirectional"))
    )
    (net (code "106") (name "unconnected-(ESP2-PadVP)") (class "Default")
      (node (ref "ESP2") (pin "VP") (pinfunction "VP_VP") (pintype "bidirectional"))
    )
    (net (code "107") (name "unconnected-(IC2A-X0-Pad13)") (class "Default")
      (node (ref "IC2") (pin "13") (pinfunction "X0_13") (pintype "bidirectional"))
    )
    (net (code "108") (name "unconnected-(IC2A-X3-Pad12)") (class "Default")
      (node (ref "IC2") (pin "12") (pinfunction "X3_12") (pintype "bidirectional"))
    )
    (net (code "109") (name "unconnected-(IC2A-X4-Pad1)") (class "Default")
      (node (ref "IC2") (pin "1") (pinfunction "X4_1") (pintype "bidirectional"))
    )
    (net (code "110") (name "unconnected-(IC2A-X5-Pad5)") (class "Default")
      (node (ref "IC2") (pin "5") (pinfunction "X5_5") (pintype "bidirectional"))
    )
    (net (code "111") (name "unconnected-(IC2A-X6-Pad2)") (class "Default")
      (node (ref "IC2") (pin "2") (pinfunction "X6_2") (pintype "bidirectional"))
    )
    (net (code "112") (name "unconnected-(IC2A-X7-Pad4)") (class "Default")
      (node (ref "IC2") (pin "4") (pinfunction "X7_4") (pintype "bidirectional"))
    )
  )
)
